# LED.net
KiCad netlist of a schematic drawn in Altium Designer
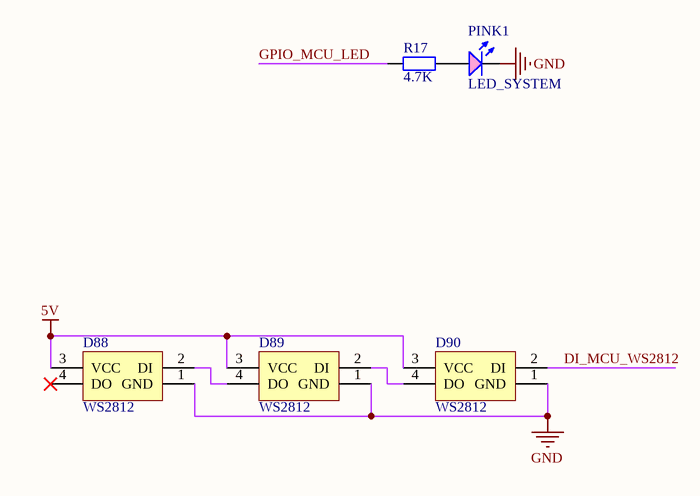
[diagram p0: LED.SchDoc]

(export (version "E")
  (design (tool "Eeschema 10.0.6"))
  (components
    (comp (ref "D88")
      (value "WS2812")
      (footprint "RGB_LED_1206")
      (fields (field (name "PUBLISHER") "mazhongwei"))
      (libsource (lib "Miscellaneous IC") (part "WS2812"))
    )
    (comp (ref "D89")
      (value "WS2812")
      (footprint "RGB_LED_1206")
      (fields (field (name "PUBLISHER") "mazhongwei"))
      (libsource (lib "Miscellaneous IC") (part "WS2812"))
    )
    (comp (ref "D90")
      (value "WS2812")
      (footprint "RGB_LED_1206")
      (fields (field (name "PUBLISHER") "mazhongwei"))
      (libsource (lib "Miscellaneous IC") (part "WS2812"))
    )
    (comp (ref "PINK1")
      (value "LED_SYSTEM")
      (footprint "LED_0603_R")
      (description "发光二极管")
      (libsource (lib "Miscellaneous Transistor") (part "LED_SMD_PINK"))
    )
    (comp (ref "R17")
      (value "4.7K")
      (footprint "Res-0603")
      (description "贴片电阻")
      (libsource (lib "Miscellaneous Base") (part "RES"))
    )
  )
  (nets
    (net (code "1") (name "/DI_MCU_WS2812") (class "Default")
      (node (ref "D90") (pin "2") (pinfunction "DI_2") (pintype "passive"))
    )
    (net (code "2") (name "/GPIO_MCU_LED") (class "Default")
      (node (ref "R17") (pin "2") (pinfunction "2_2") (pintype "passive"))
    )
    (net (code "3") (name "5V") (class "Default")
      (node (ref "D88") (pin "3") (pinfunction "VCC_3") (pintype "passive"))
      (node (ref "D89") (pin "3") (pinfunction "VCC_3") (pintype "passive"))
      (node (ref "D90") (pin "3") (pinfunction "VCC_3") (pintype "passive"))
    )
    (net (code "4") (name "GND") (class "Default")
      (node (ref "D88") (pin "1") (pinfunction "GND_1") (pintype "passive"))
      (node (ref "D89") (pin "1") (pinfunction "GND_1") (pintype "passive"))
      (node (ref "D90") (pin "1") (pinfunction "GND_1") (pintype "passive"))
      (node (ref "PINK1") (pin "2") (pinfunction "K_2") (pintype "passive"))
    )
    (net (code "5") (name "Net-(D88-DI)") (class "Default")
      (node (ref "D88") (pin "2") (pinfunction "DI_2") (pintype "passive"))
      (node (ref "D89") (pin "4") (pinfunction "DO_4") (pintype "passive"))
    )
    (net (code "6") (name "Net-(D89-DI)") (class "Default")
      (node (ref "D89") (pin "2") (pinfunction "DI_2") (pintype "passive"))
      (node (ref "D90") (pin "4") (pinfunction "DO_4") (pintype "passive"))
    )
    (net (code "7") (name "Net-(PINK1-A)") (class "Default")
      (node (ref "PINK1") (pin "1") (pinfunction "A_1") (pintype "passive"))
      (node (ref "R17") (pin "1") (pinfunction "1_1") (pintype "passive"))
    )
    (net (code "8") (name "unconnected-(D88-DO-Pad4)") (class "Default")
      (node (ref "D88") (pin "4") (pinfunction "DO_4") (pintype "passive+no_connect"))
    )
  )
)
